# regulador.net
KiCad netlist of a schematic drawn in Altium Designer
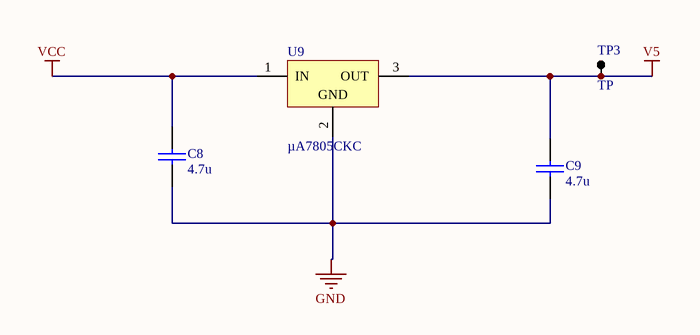
[diagram p0: regulador.SchDoc]

(export (version "E")
  (design (tool "Eeschema 10.0.6"))
  (components
    (comp (ref "C8") (value "4.7u") (footprint "0805") (libsource (lib "LIBEBAL") (part "CAP")))
    (comp (ref "C9") (value "4.7u") (footprint "0805") (libsource (lib "LIBEBAL") (part "CAP")))
    (comp (ref "TP3") (value "TP") (footprint "TPTH") (libsource (lib "LIBEBAL") (part "TP")))
    (comp (ref "U9")
      (value "µA7805CKC")
      (footprint "KC03")
      (description "Positive-Voltage Regulator")
      (fields (field (name "PUBLISHER") "Altium Limited"))
      (libsource (lib "TI Power Mgt Voltage Regulator") (part "µA7805CKC"))
    )
  )
  (nets
    (net (code "1") (name "GND") (class "Default")
      (node (ref "C8") (pin "2") (pinfunction "2_2") (pintype "passive"))
      (node (ref "C9") (pin "2") (pinfunction "2_2") (pintype "passive"))
      (node (ref "U9") (pin "2") (pinfunction "GND_2") (pintype "power_in"))
    )
    (net (code "2") (name "V5") (class "Default")
      (node (ref "C9") (pin "1") (pinfunction "1_1") (pintype "passive"))
      (node (ref "TP3") (pin "1") (pinfunction "1_1") (pintype "passive"))
      (node (ref "U9") (pin "3") (pinfunction "OUT_3") (pintype "power_in"))
    )
    (net (code "3") (name "VCC") (class "Default")
      (node (ref "C8") (pin "1") (pinfunction "1_1") (pintype "passive"))
      (node (ref "U9") (pin "1") (pinfunction "IN_1") (pintype "power_in"))
    )
  )
)
